# Power.net
KiCad netlist of a schematic drawn in Altium Designer
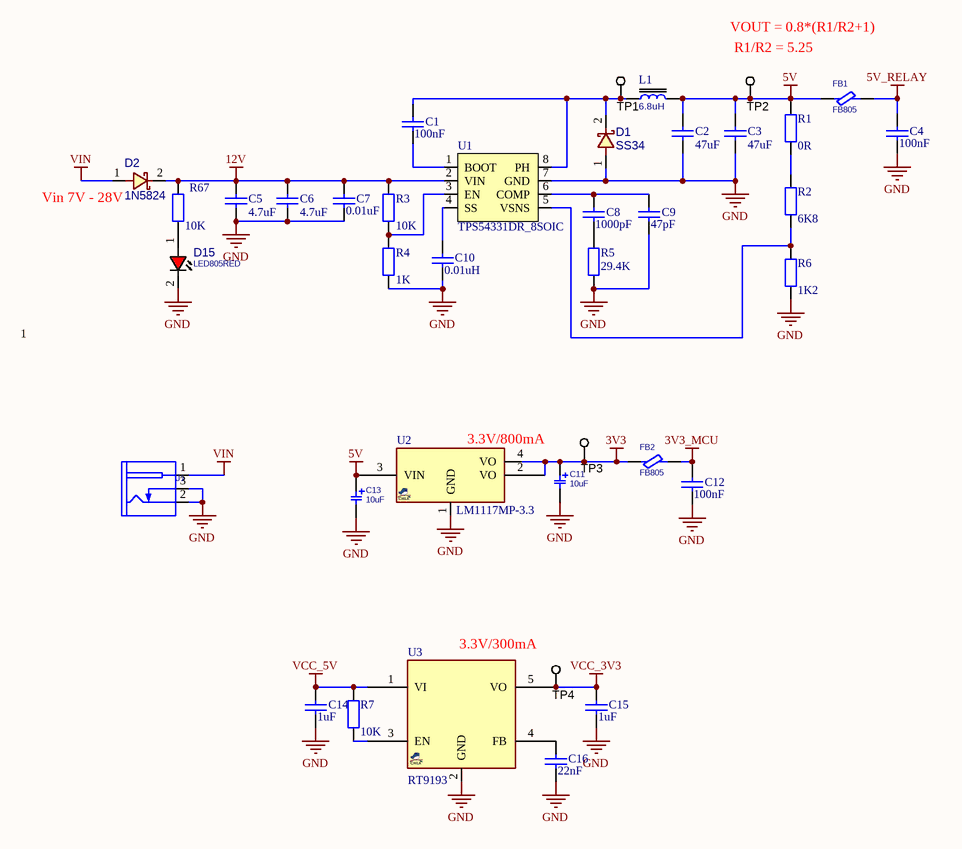
[diagram p0: Power.SchDoc]

(export (version "E")
  (design (tool "Eeschema 10.0.6"))
  (components
    (comp (ref "C1")
      (value "100nF_0603_1%")
      (footprint "tu 0603")
      (description "Capacitor, Ceramic, 50V")
      (fields (field (name "MA_HANG") "100nF"))
      (libsource (lib "THU VIEN SCH") (part "Tu 0603 470pF 50V 10%"))
    )
    (comp (ref "C2")
      (value "47uF_1206_1%")
      (footprint "tu 1206")
      (description "Capacitor, Ceramic, 50V")
      (fields (field (name "MA_HANG") "47uF"))
      (libsource (lib "THU VIEN SCH") (part "Tu 1206 103 50V 10%"))
    )
    (comp (ref "C3")
      (value "47uF_1206_1%")
      (footprint "tu 1206")
      (description "Capacitor, Ceramic, 50V")
      (fields (field (name "MA_HANG") "47uF"))
      (libsource (lib "THU VIEN SCH") (part "Tu 1206 103 50V 10%"))
    )
    (comp (ref "C4")
      (value "100nF_0603_1%")
      (footprint "tu 0603")
      (description "Capacitor, Ceramic, 50V")
      (fields (field (name "MA_HANG") "100nF"))
      (libsource (lib "THU VIEN SCH") (part "Tu 0603 470pF 50V 10%"))
    )
    (comp (ref "C5")
      (value "4.7uF_1206_1%")
      (footprint "tu 1206")
      (description "Capacitor, Ceramic, 50V")
      (fields (field (name "MA_HANG") "4.7uF"))
      (libsource (lib "THU VIEN SCH") (part "Tu 1206 103 50V 10%"))
    )
    (comp (ref "C6")
      (value "4.7uF_1206_1%")
      (footprint "tu 1206")
      (description "Capacitor, Ceramic, 50V")
      (fields (field (name "MA_HANG") "4.7uF"))
      (libsource (lib "THU VIEN SCH") (part "Tu 1206 103 50V 10%"))
    )
    (comp (ref "C7")
      (value "0.01uF_0603_1%")
      (footprint "tu 0603")
      (description "Capacitor, Ceramic, 50V")
      (fields (field (name "MA_HANG") "0.01uF"))
      (libsource (lib "THU VIEN SCH") (part "Tu 0603 470pF 50V 10%"))
    )
    (comp (ref "C8")
      (value "1000pF_0603_1%")
      (footprint "tu 0603")
      (description "Capacitor, Ceramic, 50V")
      (fields (field (name "MA_HANG") "1000pF"))
      (libsource (lib "THU VIEN SCH") (part "Tu 0603 470pF 50V 10%"))
    )
    (comp (ref "C9")
      (value "47pF_0603_1%")
      (footprint "tu 0603")
      (description "Capacitor, Ceramic, 50V")
      (fields (field (name "MA_HANG") "47pF"))
      (libsource (lib "THU VIEN SCH") (part "Tu 0603 470pF 50V 10%"))
    )
    (comp (ref "C10")
      (value "0.01uF_0603_1%")
      (footprint "tu 0603")
      (description "CAP SMD 0603")
      (fields (field (name "MA_HANG") "0.01uH"))
      (libsource (lib "THU VIEN SCH") (part "Tu 0603 470pF 50V 10%"))
    )
    (comp (ref "C11")
      (value "10uF")
      (footprint "C_TN_3216")
      (description "CAP, SMD, TAN")
      (fields (field (name "MANF") "VISHAY") (field (name "MANF_P#") "T55A106M6R3C0300"))
      (libsource (lib "AH_Library") (part "CAP_SMD_TAN_10uF_6.3V"))
    )
    (comp (ref "C12")
      (value "100nF_0603_1%")
      (footprint "tu 0603")
      (description "Capacitor, Ceramic, 50V")
      (fields (field (name "MA_HANG") "100nF"))
      (libsource (lib "THU VIEN SCH") (part "Tu 0603 470pF 50V 10%"))
    )
    (comp (ref "C13")
      (value "10uF")
      (footprint "C_TN_3216")
      (description "CAP, SMD, TAN")
      (fields (field (name "MANF") "VISHAY") (field (name "MANF_P#") "T55A106M010C0300"))
      (libsource (lib "AH_Library") (part "CAP_SMD_TAN_10uF_10V"))
    )
    (comp (ref "C14")
      (value "1uF_0603_1%")
      (footprint "tu 0603")
      (description "Capacitor, Ceramic, 50V")
      (fields (field (name "MA_HANG") "1uF"))
      (libsource (lib "THU VIEN SCH") (part "Tu 0603 470pF 50V 10%"))
    )
    (comp (ref "C15")
      (value "1uF_0603_1%")
      (footprint "tu 0603")
      (description "Capacitor, Ceramic, 50V")
      (fields (field (name "MA_HANG") "1uF"))
      (libsource (lib "THU VIEN SCH") (part "Tu 0603 470pF 50V 10%"))
    )
    (comp (ref "C16")
      (value "22nF_0603_1%")
      (footprint "tu 0603")
      (description "Capacitor, Ceramic, 50V")
      (fields (field (name "MA_HANG") "22nF"))
      (libsource (lib "THU VIEN SCH") (part "Tu 0603 470pF 50V 10%"))
    )
    (comp (ref "D1")
      (value "SS34")
      (footprint "D_SMB")
      (description "DIODE, SCHOTTKY, 20V, 3A")
      (fields (field (name "MANF") "VISHAY") (field (name "Comment") "SS34_SMA"))
      (libsource (lib "AH_Library") (part "DIODE_SMD_SCHOTTKY_SS34"))
    )
    (comp (ref "D2")
      (value "1N5824")
      (footprint "D_SMA")
      (description "DIODE, SCHOTTKY, 40V, 3A")
      (fields (field (name "MANF") "DIODES") (field (name "MANF_P#") "1N5822"))
      (libsource (lib "AH_Library") (part "DIODE_SMD_SCHOTTKY_1N5822"))
    )
    (comp (ref "D15")
      (value "LED805RED")
      (footprint "LED0805RED")
      (description "LED, SMD, 0805, RED")
      (fields (field (name "MANF") "MANF") (field (name "MANF_P#") "MANF_PART#"))
      (libsource (lib "AH_Library") (part "LED_SMD_0805_RED"))
    )
    (comp (ref "FB1")
      (value "FB805")
      (footprint "L0805")
      (description "FERRITE_Bead, 0805, 2A, 50mOhm, 220@100MHz")
      (fields (field (name "MANF") "MURATA") (field (name "MANF_P#") "BLM15AG121SN1D"))
      (libsource (lib "AH_Library") (part "FBEAD_SMD_BLM21PG221"))
    )
    (comp (ref "FB2")
      (value "FB805")
      (footprint "L0805")
      (description "FERRITE_Bead, 0805, 2A, 50mOhm, 220@100MHz")
      (fields (field (name "MANF") "MURATA") (field (name "MANF_P#") "BLM15AG121SN1D"))
      (libsource (lib "AH_Library") (part "FBEAD_SMD_BLM21PG221"))
    )
    (comp (ref "J1")
      (value "DC_POWER_JACK")
      (footprint "JAC_PWR2")
      (description "CONN, PWR JACK DC, PLUG DIAM 2.0MM RA THD")
      (fields
        (field (name "MANF") "CUI STACK")
        (field (name "MANF_P#") "PJ-202A, PJ-002AH, PJ-102AH, KLDX-0202")
      )
      (libsource (lib "AH_Library") (part "CONN_PWR_JACKR2"))
    )
    (comp (ref "L1")
      (value "6.8uH")
      (footprint "L_10")
      (description "INDUCTOR, POWER, SMD")
      (fields (field (name "Comment") "6.8uH_CD104"))
      (libsource (lib "AH_Library") (part "INDPWR_SMD"))
    )
    (comp (ref "R1")
      (value "0R_0603_1%")
      (footprint "tro smd 0603")
      (description "RES SMD 0603")
      (fields (field (name "MA_HANG") "0R"))
      (libsource (lib "THU VIEN SCH") (part "Tro 0603 5% 10k"))
    )
    (comp (ref "R2")
      (value "6K8_0603_1%")
      (footprint "tro smd 0603")
      (description "RES SMD 0603")
      (fields (field (name "MA_HANG") "6K8"))
      (libsource (lib "THU VIEN SCH") (part "Tro 0603 5% 10k"))
    )
    (comp (ref "R3")
      (value "10K_0603_1%")
      (footprint "tro smd 0603")
      (description "RES SMD 0603")
      (fields (field (name "MA_HANG") "10K"))
      (libsource (lib "THU VIEN SCH") (part "Tro 0603 5% 10k"))
    )
    (comp (ref "R4")
      (value "1K_0603_1%")
      (footprint "tro smd 0603")
      (description "RES SMD 0603")
      (fields (field (name "MA_HANG") "1K"))
      (libsource (lib "THU VIEN SCH") (part "Tro 0603 5% 10k"))
    )
    (comp (ref "R5")
      (value "29.4K_0805_1%")
      (footprint "tro smd 0805")
      (description "Dán")
      (fields (field (name "MA_HANG") "29.4K"))
      (libsource (lib "THU VIEN SCH") (part "Tro 0805 1% 5.1k"))
    )
    (comp (ref "R6")
      (value "1K2_0603_1%")
      (footprint "tro smd 0603")
      (description "RES SMD 0603")
      (fields (field (name "MA_HANG") "1K2"))
      (libsource (lib "THU VIEN SCH") (part "Tro 0603 5% 10k"))
    )
    (comp (ref "R7")
      (value "10K_0603_1%")
      (footprint "tro smd 0603")
      (description "RES SMD 0603")
      (fields (field (name "MA_HANG") "10K"))
      (libsource (lib "THU VIEN SCH") (part "Tro 0603 5% 10k"))
    )
    (comp (ref "R67")
      (value "10K_0603_1%")
      (footprint "tro smd 0603")
      (description "RES SMD 0603")
      (fields (field (name "MA_HANG") "10K"))
      (libsource (lib "THU VIEN SCH") (part "Tro 0603 5% 10k"))
    )
    (comp (ref "TP1")
      (value "TESTPOINT_PROBE")
      (footprint "TEST_POINT_1.0X1.0MM")
      (description "TEST POINT")
      (fields (field (name "MANF") "MANF") (field (name "MANF_P#") "MANF_P#"))
      (libsource (lib "AH_Library") (part "TESTPOINT_PROBE"))
    )
    (comp (ref "TP2")
      (value "TESTPOINT_PROBE")
      (footprint "TEST_POINT_1.0X1.0MM")
      (description "TEST POINT")
      (fields (field (name "MANF") "MANF") (field (name "MANF_P#") "MANF_P#"))
      (libsource (lib "AH_Library") (part "TESTPOINT_PROBE"))
    )
    (comp (ref "TP3")
      (value "TESTPOINT_PROBE")
      (footprint "TEST_POINT_1.0X1.0MM")
      (description "TEST POINT")
      (fields (field (name "MANF") "MANF") (field (name "MANF_P#") "MANF_P#"))
      (libsource (lib "AH_Library") (part "TESTPOINT_PROBE"))
    )
    (comp (ref "TP4")
      (value "TESTPOINT_PROBE")
      (footprint "TEST_POINT_1.0X1.0MM")
      (description "TEST POINT")
      (fields (field (name "MANF") "MANF") (field (name "MANF_P#") "MANF_P#"))
      (libsource (lib "AH_Library") (part "TESTPOINT_PROBE"))
    )
    (comp (ref "U1")
      (value "TPS54331DR_8SOIC")
      (footprint "SOIC-8N")
      (description "IC REG BUCK ADJ 3A 8SOIC")
      (libsource (lib "PCB_Project_Dangrangto") (part "TPS54331DR"))
    )
    (comp (ref "U2")
      (value "LM1117MP-3.3")
      (footprint "SOT223_4")
      (description "REG, Linear, LDO1V, 0.8A, SOT-223")
      (fields
        (field (name "MANF_P#") "LD1117, LM1117, AMS1117, TLV1117, REG1117, NCP1117, LT1117, SPX1117")
        (field (name "MANF") "TI, ON, ST")
      )
      (libsource (lib "AH_Library") (part "VREG_1117_SOT223"))
    )
    (comp (ref "U3")
      (value "RT9193")
      (footprint "SOT23_5")
      (description "REG, Linear, LDO, SOT-23-5")
      (libsource (lib "AH_Library") (part "VREG_LDO_SOT23_5"))
    )
  )
  (nets
    (net (code "1") (name "3V3") (class "Default")
      (node (ref "C11") (pin "1") (pinfunction "1_1") (pintype "passive"))
      (node (ref "FB2") (pin "1") (pinfunction "1_1") (pintype "passive"))
      (node (ref "TP3") (pin "1") (pinfunction "1_1") (pintype "passive"))
      (node (ref "U2") (pin "2") (pinfunction "VO_2") (pintype "passive"))
      (node (ref "U2") (pin "4") (pinfunction "VO_4") (pintype "passive"))
    )
    (net (code "2") (name "3V3_MCU") (class "Default")
      (node (ref "C12") (pin "1") (pinfunction "1_1") (pintype "passive"))
      (node (ref "FB2") (pin "2") (pinfunction "2_2") (pintype "passive"))
    )
    (net (code "3") (name "5V") (class "Default")
      (node (ref "C13") (pin "1") (pinfunction "1_1") (pintype "passive"))
      (node (ref "C2") (pin "1") (pinfunction "1_1") (pintype "passive"))
      (node (ref "C3") (pin "1") (pinfunction "1_1") (pintype "passive"))
      (node (ref "FB1") (pin "1") (pinfunction "1_1") (pintype "passive"))
      (node (ref "L1") (pin "2") (pinfunction "2_2") (pintype "passive"))
      (node (ref "R1") (pin "2") (pinfunction "2_2") (pintype "passive"))
      (node (ref "TP2") (pin "1") (pinfunction "1_1") (pintype "passive"))
      (node (ref "U2") (pin "3") (pinfunction "VIN_3") (pintype "passive"))
    )
    (net (code "4") (name "5V_RELAY") (class "Default")
      (node (ref "C4") (pin "1") (pinfunction "1_1") (pintype "passive"))
      (node (ref "FB1") (pin "2") (pinfunction "2_2") (pintype "passive"))
    )
    (net (code "5") (name "12V") (class "Default")
      (node (ref "C5") (pin "1") (pinfunction "1_1") (pintype "passive"))
      (node (ref "C6") (pin "1") (pinfunction "1_1") (pintype "passive"))
      (node (ref "C7") (pin "1") (pinfunction "1_1") (pintype "passive"))
      (node (ref "D2") (pin "2") (pinfunction "2_2") (pintype "passive"))
      (node (ref "R3") (pin "2") (pinfunction "2_2") (pintype "passive"))
      (node (ref "R67") (pin "2") (pinfunction "2_2") (pintype "passive"))
      (node (ref "U1") (pin "2") (pinfunction "VIN_2") (pintype "passive"))
    )
    (net (code "6") (name "GND") (class "Default")
      (node (ref "C10") (pin "2") (pinfunction "2_2") (pintype "passive"))
      (node (ref "C11") (pin "2") (pinfunction "2_2") (pintype "passive"))
      (node (ref "C12") (pin "2") (pinfunction "2_2") (pintype "passive"))
      (node (ref "C13") (pin "2") (pinfunction "2_2") (pintype "passive"))
      (node (ref "C14") (pin "2") (pinfunction "2_2") (pintype "passive"))
      (node (ref "C15") (pin "2") (pinfunction "2_2") (pintype "passive"))
      (node (ref "C16") (pin "2") (pinfunction "2_2") (pintype "passive"))
      (node (ref "C2") (pin "2") (pinfunction "2_2") (pintype "passive"))
      (node (ref "C3") (pin "2") (pinfunction "2_2") (pintype "passive"))
      (node (ref "C4") (pin "2") (pinfunction "2_2") (pintype "passive"))
      (node (ref "C5") (pin "2") (pinfunction "2_2") (pintype "passive"))
      (node (ref "C6") (pin "2") (pinfunction "2_2") (pintype "passive"))
      (node (ref "C7") (pin "2") (pinfunction "2_2") (pintype "passive"))
      (node (ref "C9") (pin "2") (pinfunction "2_2") (pintype "passive"))
      (node (ref "D1") (pin "1") (pinfunction "1_1") (pintype "passive"))
      (node (ref "D15") (pin "2") (pinfunction "CATHODE_2") (pintype "passive"))
      (node (ref "J1") (pin "2") (pinfunction "SLEEVE_2") (pintype "power_in"))
      (node (ref "J1") (pin "3") (pinfunction "INSERTION_DET_3") (pintype "power_in"))
      (node (ref "R4") (pin "1") (pinfunction "1_1") (pintype "passive"))
      (node (ref "R5") (pin "1") (pinfunction "1_1") (pintype "passive"))
      (node (ref "R6") (pin "1") (pinfunction "1_1") (pintype "passive"))
      (node (ref "U1") (pin "7") (pinfunction "GND_7") (pintype "passive"))
      (node (ref "U2") (pin "1") (pinfunction "GND_1") (pintype "passive"))
      (node (ref "U3") (pin "2") (pinfunction "GND_2") (pintype "passive"))
    )
    (net (code "7") (name "Net-(C8-Pad2)") (class "Default")
      (node (ref "C8") (pin "2") (pinfunction "2_2") (pintype "passive"))
      (node (ref "R5") (pin "2") (pinfunction "2_2") (pintype "passive"))
    )
    (net (code "8") (name "Net-(D15-ANODE)") (class "Default")
      (node (ref "D15") (pin "1") (pinfunction "ANODE_1") (pintype "passive"))
      (node (ref "R67") (pin "1") (pinfunction "1_1") (pintype "passive"))
    )
    (net (code "9") (name "Net-(R1-Pad1)") (class "Default")
      (node (ref "R1") (pin "1") (pinfunction "1_1") (pintype "passive"))
      (node (ref "R2") (pin "2") (pinfunction "2_2") (pintype "passive"))
    )
    (net (code "10") (name "Net-(U1-BOOT)") (class "Default")
      (node (ref "C1") (pin "2") (pinfunction "2_2") (pintype "passive"))
      (node (ref "U1") (pin "1") (pinfunction "BOOT_1") (pintype "passive"))
    )
    (net (code "11") (name "Net-(U1-COMP)") (class "Default")
      (node (ref "C8") (pin "1") (pinfunction "1_1") (pintype "passive"))
      (node (ref "C9") (pin "1") (pinfunction "1_1") (pintype "passive"))
      (node (ref "U1") (pin "6") (pinfunction "COMP_6") (pintype "passive"))
    )
    (net (code "12") (name "Net-(U1-EN)") (class "Default")
      (node (ref "R3") (pin "1") (pinfunction "1_1") (pintype "passive"))
      (node (ref "R4") (pin "2") (pinfunction "2_2") (pintype "passive"))
      (node (ref "U1") (pin "3") (pinfunction "EN_3") (pintype "passive"))
    )
    (net (code "13") (name "Net-(U1-PH)") (class "Default")
      (node (ref "C1") (pin "1") (pinfunction "1_1") (pintype "passive"))
      (node (ref "D1") (pin "2") (pinfunction "2_2") (pintype "passive"))
      (node (ref "L1") (pin "1") (pinfunction "1_1") (pintype "passive"))
      (node (ref "TP1") (pin "1") (pinfunction "1_1") (pintype "passive"))
      (node (ref "U1") (pin "8") (pinfunction "PH_8") (pintype "passive"))
    )
    (net (code "14") (name "Net-(U1-SS)") (class "Default")
      (node (ref "C10") (pin "1") (pinfunction "1_1") (pintype "passive"))
      (node (ref "U1") (pin "4") (pinfunction "SS_4") (pintype "passive"))
    )
    (net (code "15") (name "Net-(U1-VSNS)") (class "Default")
      (node (ref "R2") (pin "1") (pinfunction "1_1") (pintype "passive"))
      (node (ref "R6") (pin "2") (pinfunction "2_2") (pintype "passive"))
      (node (ref "U1") (pin "5") (pinfunction "VSNS_5") (pintype "passive"))
    )
    (net (code "16") (name "Net-(U3-EN)") (class "Default")
      (node (ref "R7") (pin "1") (pinfunction "1_1") (pintype "passive"))
      (node (ref "U3") (pin "3") (pinfunction "EN_3") (pintype "passive"))
    )
    (net (code "17") (name "Net-(U3-FB)") (class "Default")
      (node (ref "C16") (pin "1") (pinfunction "1_1") (pintype "passive"))
      (node (ref "U3") (pin "4") (pinfunction "FB_4") (pintype "passive"))
    )
    (net (code "18") (name "VCC_3V3") (class "Default")
      (node (ref "C15") (pin "1") (pinfunction "1_1") (pintype "passive"))
      (node (ref "TP4") (pin "1") (pinfunction "1_1") (pintype "passive"))
      (node (ref "U3") (pin "5") (pinfunction "VO_5") (pintype "passive"))
    )
    (net (code "19") (name "VCC_5V") (class "Default")
      (node (ref "C14") (pin "1") (pinfunction "1_1") (pintype "passive"))
      (node (ref "R7") (pin "2") (pinfunction "2_2") (pintype "passive"))
      (node (ref "U3") (pin "1") (pinfunction "VI_1") (pintype "passive"))
    )
    (net (code "20") (name "VIN") (class "Default")
      (node (ref "D2") (pin "1") (pinfunction "1_1") (pintype "passive"))
      (node (ref "J1") (pin "1") (pinfunction "TIP_1") (pintype "power_in"))
    )
  )
)
